# MicorMouse2020Classic-Servos.net
KiCad netlist of a schematic drawn in EAGLE
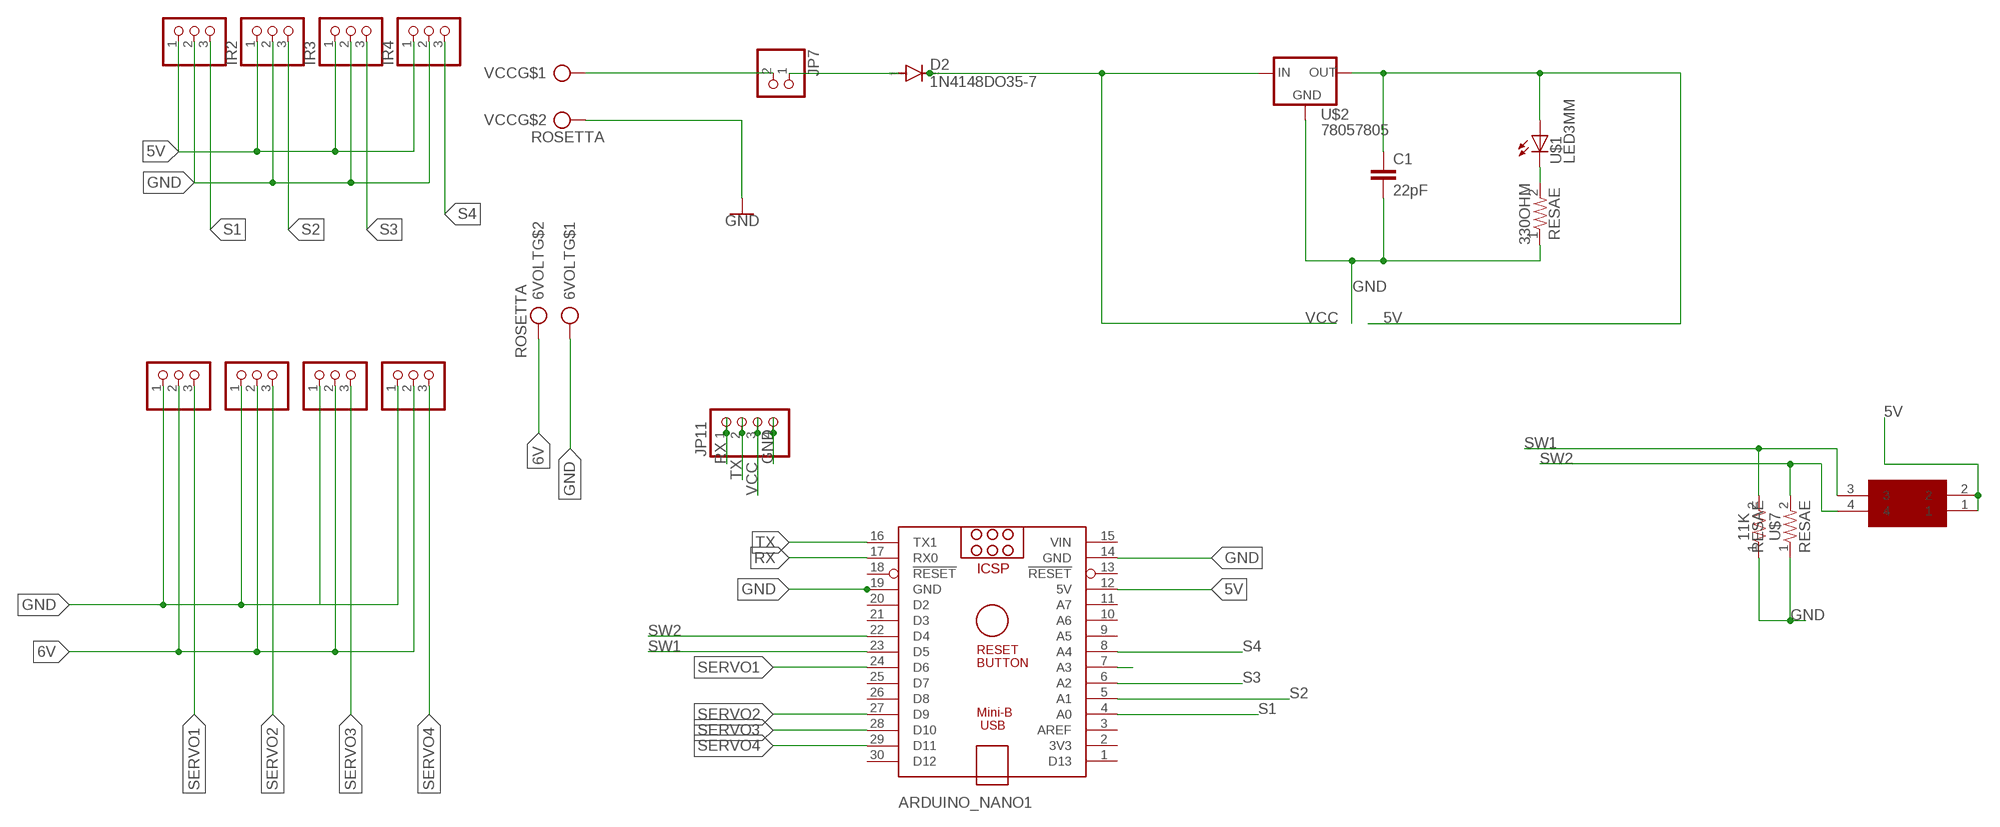
[diagram p0: schematic, sheet 1]

(export (version "E")
  (design (tool "Eeschema 10.0.6"))
  (components
    (comp (ref "6VOLT")
      (value "ROSETTA")
      (footprint "eagle-import:AK550_2")
      (libsource (lib "eagle-import") (part "ROSETTA"))
    )
    (comp (ref "11K")
      (value "RESAE")
      (footprint "eagle-import:RESAD846W63L520D250B")
      (libsource (lib "eagle-import") (part "RESAE"))
    )
    (comp (ref "330OHM")
      (value "RESAE")
      (footprint "eagle-import:RESAD846W63L520D250B")
      (libsource (lib "eagle-import") (part "RESAE"))
    )
    (comp (ref "ARDUINO_NANO1")
      (value "ARDUINO_NANO")
      (footprint "eagle-import:ARDUINO_NANO")
      (libsource (lib "eagle-import") (part "ARDUINO_NANO"))
    )
    (comp (ref "C1")
      (value "22pF")
      (footprint "eagle-import:CAP-PTH-2.54")
      (libsource (lib "eagle-import") (part "22PF-PTH-2.54MM-200V-5%"))
    )
    (comp (ref "D2")
      (value "1N4148DO35-7")
      (footprint "eagle-import:DO35-7")
      (libsource (lib "eagle-import") (part "1N4148DO35-7"))
    )
    (comp (ref "IR1")
      (value "PINHD-1X3")
      (footprint "eagle-import:1X03")
      (libsource (lib "eagle-import") (part "PINHD-1X3"))
    )
    (comp (ref "IR2")
      (value "PINHD-1X3")
      (footprint "eagle-import:1X03")
      (libsource (lib "eagle-import") (part "PINHD-1X3"))
    )
    (comp (ref "IR3")
      (value "PINHD-1X3")
      (footprint "eagle-import:1X03")
      (libsource (lib "eagle-import") (part "PINHD-1X3"))
    )
    (comp (ref "IR4")
      (value "PINHD-1X3")
      (footprint "eagle-import:1X03")
      (libsource (lib "eagle-import") (part "PINHD-1X3"))
    )
    (comp (ref "JP7")
      (value "PINHD-1X2")
      (footprint "eagle-import:1X02")
      (libsource (lib "eagle-import") (part "PINHD-1X2"))
    )
    (comp (ref "JP11")
      (value "PINHD-1X4/90")
      (footprint "eagle-import:1X04_90")
      (libsource (lib "eagle-import") (part "PINHD-1X4/90"))
    )
    (comp (ref "SERVO1")
      (value "PINHD-1X3")
      (footprint "eagle-import:1X03")
      (libsource (lib "eagle-import") (part "PINHD-1X3"))
    )
    (comp (ref "SERVO2")
      (value "PINHD-1X3")
      (footprint "eagle-import:1X03")
      (libsource (lib "eagle-import") (part "PINHD-1X3"))
    )
    (comp (ref "SERVO3")
      (value "PINHD-1X3")
      (footprint "eagle-import:1X03")
      (libsource (lib "eagle-import") (part "PINHD-1X3"))
    )
    (comp (ref "SERVO4")
      (value "PINHD-1X3")
      (footprint "eagle-import:1X03")
      (libsource (lib "eagle-import") (part "PINHD-1X3"))
    )
    (comp (ref "U$1")
      (value "LED3MM")
      (footprint "eagle-import:LEDRD254W60D310H860B")
      (libsource (lib "eagle-import") (part "LED3MM"))
    )
    (comp (ref "U$2")
      (value "78057805")
      (footprint "eagle-import:T-30_V")
      (libsource (lib "eagle-import") (part "78057805"))
    )
    (comp (ref "U$7")
      (value "RESAE")
      (footprint "eagle-import:RESAD846W63L520D250B")
      (libsource (lib "eagle-import") (part "RESAE"))
    )
    (comp (ref "U$8")
      (value "AE-DIP")
      (footprint "eagle-import:EPG-02")
      (libsource (lib "eagle-import") (part "AE-DIP"))
    )
    (comp (ref "VCC")
      (value "ROSETTA")
      (footprint "eagle-import:AK550_2")
      (libsource (lib "eagle-import") (part "ROSETTA"))
    )
  )
  (nets
    (net (code "1") (name "/SW1") (class "Default")
      (node (ref "11K") (pin "2") (pinfunction "2_2") (pintype "passive"))
      (node (ref "ARDUINO_NANO1") (pin "23") (pinfunction "D5_23") (pintype "bidirectional"))
      (node (ref "U$8") (pin "3") (pinfunction "3_3") (pintype "bidirectional"))
    )
    (net (code "2") (name "/SW2") (class "Default")
      (node (ref "ARDUINO_NANO1") (pin "22") (pinfunction "D4_22") (pintype "bidirectional"))
      (node (ref "U$7") (pin "2") (pinfunction "2_2") (pintype "passive"))
      (node (ref "U$8") (pin "4") (pinfunction "4_4") (pintype "bidirectional"))
    )
    (net (code "3") (name "/VCC") (class "Default")
      (node (ref "D2") (pin "C") (pinfunction "C_C") (pintype "passive"))
      (node (ref "JP11") (pin "3") (pinfunction "3_3") (pintype "passive"))
      (node (ref "U$2") (pin "1") (pinfunction "IN_1") (pintype "input"))
    )
    (net (code "4") (name "/VIN") (class "Default")
      (node (ref "ARDUINO_NANO1") (pin "15") (pinfunction "VIN_15") (pintype "power_in"))
    )
    (net (code "5") (name "5V") (class "Default")
      (node (ref "ARDUINO_NANO1") (pin "12") (pinfunction "5V_12") (pintype "power_in"))
      (node (ref "C1") (pin "1") (pinfunction "1_1") (pintype "passive"))
      (node (ref "IR1") (pin "1") (pinfunction "1_1") (pintype "passive"))
      (node (ref "IR2") (pin "1") (pinfunction "1_1") (pintype "passive"))
      (node (ref "IR3") (pin "1") (pinfunction "1_1") (pintype "passive"))
      (node (ref "IR4") (pin "1") (pinfunction "1_1") (pintype "passive"))
      (node (ref "U$1") (pin "A") (pinfunction "A_A") (pintype "passive"))
      (node (ref "U$2") (pin "3") (pinfunction "OUT_3") (pintype "passive"))
      (node (ref "U$8") (pin "1") (pinfunction "1_1") (pintype "bidirectional"))
      (node (ref "U$8") (pin "2") (pinfunction "2_2") (pintype "bidirectional"))
    )
    (net (code "6") (name "6V") (class "Default")
      (node (ref "6VOLT") (pin "2") (pinfunction "KL_2") (pintype "passive"))
      (node (ref "SERVO1") (pin "2") (pinfunction "2_2") (pintype "passive"))
      (node (ref "SERVO2") (pin "2") (pinfunction "2_2") (pintype "passive"))
      (node (ref "SERVO3") (pin "2") (pinfunction "2_2") (pintype "passive"))
      (node (ref "SERVO4") (pin "2") (pinfunction "2_2") (pintype "passive"))
    )
    (net (code "7") (name "GND") (class "Default")
      (node (ref "11K") (pin "1") (pinfunction "1_1") (pintype "passive"))
      (node (ref "330OHM") (pin "1") (pinfunction "1_1") (pintype "passive"))
      (node (ref "6VOLT") (pin "1") (pinfunction "KL_1") (pintype "passive"))
      (node (ref "ARDUINO_NANO1") (pin "14") (pinfunction "GND_14") (pintype "power_in"))
      (node (ref "ARDUINO_NANO1") (pin "19") (pinfunction "GND_19") (pintype "power_in"))
      (node (ref "C1") (pin "2") (pinfunction "2_2") (pintype "passive"))
      (node (ref "IR1") (pin "2") (pinfunction "2_2") (pintype "passive"))
      (node (ref "IR2") (pin "2") (pinfunction "2_2") (pintype "passive"))
      (node (ref "IR3") (pin "2") (pinfunction "2_2") (pintype "passive"))
      (node (ref "IR4") (pin "2") (pinfunction "2_2") (pintype "passive"))
      (node (ref "JP11") (pin "4") (pinfunction "4_4") (pintype "passive"))
      (node (ref "SERVO1") (pin "1") (pinfunction "1_1") (pintype "passive"))
      (node (ref "SERVO2") (pin "1") (pinfunction "1_1") (pintype "passive"))
      (node (ref "SERVO3") (pin "1") (pinfunction "1_1") (pintype "passive"))
      (node (ref "SERVO4") (pin "1") (pinfunction "1_1") (pintype "passive"))
      (node (ref "U$2") (pin "2") (pinfunction "GND_2") (pintype "input"))
      (node (ref "U$7") (pin "1") (pinfunction "1_1") (pintype "passive"))
      (node (ref "VCC") (pin "2") (pinfunction "KL_2") (pintype "passive"))
    )
    (net (code "8") (name "Net-(330OHM-Pad2)") (class "Default")
      (node (ref "330OHM") (pin "2") (pinfunction "2_2") (pintype "passive"))
      (node (ref "U$1") (pin "C") (pinfunction "C_C") (pintype "passive"))
    )
    (net (code "9") (name "Net-(D2-PadA)") (class "Default")
      (node (ref "D2") (pin "A") (pinfunction "A_A") (pintype "passive"))
      (node (ref "JP7") (pin "1") (pinfunction "1_1") (pintype "passive"))
    )
    (net (code "10") (name "Net-(VCCA-KL)") (class "Default")
      (node (ref "JP7") (pin "2") (pinfunction "2_2") (pintype "passive"))
      (node (ref "VCC") (pin "1") (pinfunction "KL_1") (pintype "passive"))
    )
    (net (code "11") (name "RX") (class "Default")
      (node (ref "ARDUINO_NANO1") (pin "17") (pinfunction "RX0_17") (pintype "bidirectional"))
      (node (ref "JP11") (pin "1") (pinfunction "1_1") (pintype "passive"))
    )
    (net (code "12") (name "S1") (class "Default")
      (node (ref "ARDUINO_NANO1") (pin "4") (pinfunction "A0_4") (pintype "bidirectional"))
      (node (ref "IR1") (pin "3") (pinfunction "3_3") (pintype "passive"))
    )
    (net (code "13") (name "S2") (class "Default")
      (node (ref "ARDUINO_NANO1") (pin "5") (pinfunction "A1_5") (pintype "bidirectional"))
      (node (ref "IR2") (pin "3") (pinfunction "3_3") (pintype "passive"))
    )
    (net (code "14") (name "S3") (class "Default")
      (node (ref "ARDUINO_NANO1") (pin "6") (pinfunction "A2_6") (pintype "bidirectional"))
      (node (ref "IR3") (pin "3") (pinfunction "3_3") (pintype "passive"))
    )
    (net (code "15") (name "S4") (class "Default")
      (node (ref "ARDUINO_NANO1") (pin "8") (pinfunction "A4_8") (pintype "bidirectional"))
      (node (ref "IR4") (pin "3") (pinfunction "3_3") (pintype "passive"))
    )
    (net (code "16") (name "SERVO1") (class "Default")
      (node (ref "ARDUINO_NANO1") (pin "24") (pinfunction "D6_24") (pintype "bidirectional"))
      (node (ref "SERVO4") (pin "3") (pinfunction "3_3") (pintype "passive"))
    )
    (net (code "17") (name "SERVO2") (class "Default")
      (node (ref "ARDUINO_NANO1") (pin "27") (pinfunction "D9_27") (pintype "bidirectional"))
      (node (ref "SERVO3") (pin "3") (pinfunction "3_3") (pintype "passive"))
    )
    (net (code "18") (name "SERVO3") (class "Default")
      (node (ref "ARDUINO_NANO1") (pin "28") (pinfunction "D10_28") (pintype "bidirectional"))
      (node (ref "SERVO2") (pin "3") (pinfunction "3_3") (pintype "passive"))
    )
    (net (code "19") (name "SERVO4") (class "Default")
      (node (ref "ARDUINO_NANO1") (pin "29") (pinfunction "D11_29") (pintype "bidirectional"))
      (node (ref "SERVO1") (pin "3") (pinfunction "3_3") (pintype "passive"))
    )
    (net (code "20") (name "TX") (class "Default")
      (node (ref "ARDUINO_NANO1") (pin "16") (pinfunction "TX1_16") (pintype "bidirectional"))
      (node (ref "JP11") (pin "2") (pinfunction "2_2") (pintype "passive"))
    )
    (net (code "21") (name "unconnected-(ARDUINO_NANO1-3V3-Pad2)") (class "Default")
      (node (ref "ARDUINO_NANO1") (pin "2") (pinfunction "3V3_2") (pintype "output"))
    )
    (net (code "22") (name "unconnected-(ARDUINO_NANO1-A3-Pad7)") (class "Default")
      (node (ref "ARDUINO_NANO1") (pin "7") (pinfunction "A3_7") (pintype "bidirectional"))
    )
    (net (code "23") (name "unconnected-(ARDUINO_NANO1-A5-Pad9)") (class "Default")
      (node (ref "ARDUINO_NANO1") (pin "9") (pinfunction "A5_9") (pintype "bidirectional"))
    )
    (net (code "24") (name "unconnected-(ARDUINO_NANO1-A6-Pad10)") (class "Default")
      (node (ref "ARDUINO_NANO1") (pin "10") (pinfunction "A6_10") (pintype "bidirectional"))
    )
    (net (code "25") (name "unconnected-(ARDUINO_NANO1-A7-Pad11)") (class "Default")
      (node (ref "ARDUINO_NANO1") (pin "11") (pinfunction "A7_11") (pintype "bidirectional"))
    )
    (net (code "26") (name "unconnected-(ARDUINO_NANO1-AREF-Pad3)") (class "Default")
      (node (ref "ARDUINO_NANO1") (pin "3") (pinfunction "AREF_3") (pintype "input"))
    )
    (net (code "27") (name "unconnected-(ARDUINO_NANO1-D2-Pad20)") (class "Default")
      (node (ref "ARDUINO_NANO1") (pin "20") (pinfunction "D2_20") (pintype "bidirectional"))
    )
    (net (code "28") (name "unconnected-(ARDUINO_NANO1-D3-Pad21)") (class "Default")
      (node (ref "ARDUINO_NANO1") (pin "21") (pinfunction "D3_21") (pintype "bidirectional"))
    )
    (net (code "29") (name "unconnected-(ARDUINO_NANO1-D7-Pad25)") (class "Default")
      (node (ref "ARDUINO_NANO1") (pin "25") (pinfunction "D7_25") (pintype "bidirectional"))
    )
    (net (code "30") (name "unconnected-(ARDUINO_NANO1-D8-Pad26)") (class "Default")
      (node (ref "ARDUINO_NANO1") (pin "26") (pinfunction "D8_26") (pintype "bidirectional"))
    )
    (net (code "31") (name "unconnected-(ARDUINO_NANO1-D12-Pad30)") (class "Default")
      (node (ref "ARDUINO_NANO1") (pin "30") (pinfunction "D12_30") (pintype "bidirectional"))
    )
    (net (code "32") (name "unconnected-(ARDUINO_NANO1-D13-Pad1)") (class "Default")
      (node (ref "ARDUINO_NANO1") (pin "1") (pinfunction "D13_1") (pintype "bidirectional"))
    )
    (net (code "33") (name "unconnected-(ARDUINO_NANO1-~{RESET}-Pad13)") (class "Default")
      (node (ref "ARDUINO_NANO1") (pin "13") (pinfunction "~{RESET}_13") (pintype "input"))
    )
    (net (code "34") (name "unconnected-(ARDUINO_NANO1-~{RESET}-Pad18)") (class "Default")
      (node (ref "ARDUINO_NANO1") (pin "18") (pinfunction "~{RESET}_18") (pintype "input"))
    )
  )
)
